# Mainboard.net
KiCad netlist of a schematic drawn in EAGLE
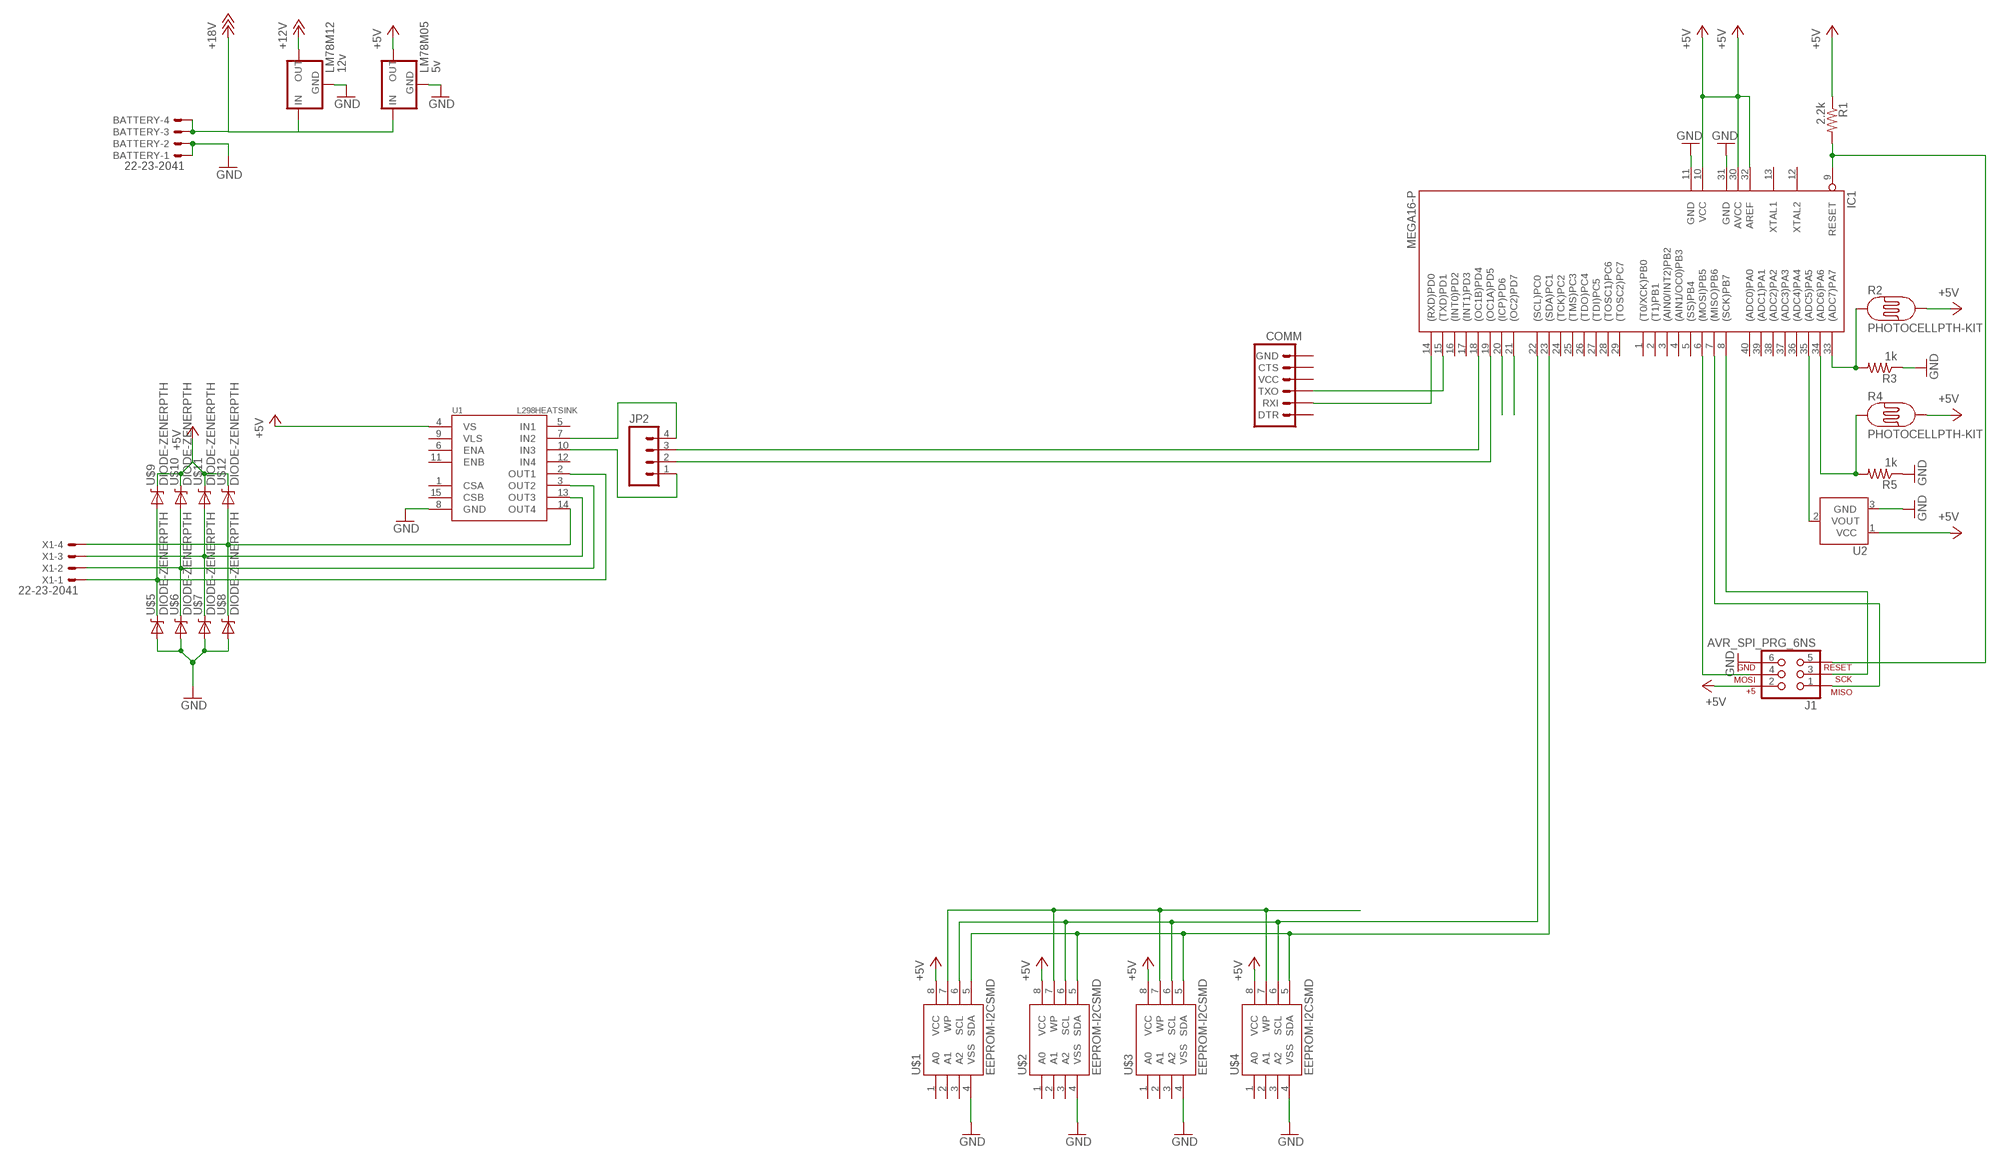
[diagram p0: schematic, sheet 1]

(export (version "E")
  (design (tool "Eeschema 10.0.6"))
  (components
    (comp (ref "BATTERY")
      (value "22-23-2041")
      (footprint "eagle-import:22-23-2041")
      (fields (field (name "MF") "MOLEX"))
      (libsource (lib "eagle-import") (part "22-23-2041"))
    )
    (comp (ref "COMM")
      (value "ARDUINO_SERIAL_PROGRAMPTH")
      (footprint "eagle-import:1X06")
      (libsource (lib "eagle-import") (part "ARDUINO_SERIAL_PROGRAMPTH"))
    )
    (comp (ref "IC1")
      (value "MEGA16-P")
      (footprint "eagle-import:DIL40")
      (fields (field (name "MPN") "ATMEGA16-16PU"))
      (libsource (lib "eagle-import") (part "MEGA16-P"))
    )
    (comp (ref "J1")
      (value "AVR_SPI_PRG_6NS")
      (footprint "eagle-import:2X3-NS")
      (libsource (lib "eagle-import") (part "AVR_SPI_PRG_6NS"))
    )
    (comp (ref "JP2")
      (value "M04PTH")
      (footprint "eagle-import:1X04")
      (libsource (lib "eagle-import") (part "M04PTH"))
    )
    (comp (ref "LM78M05")
      (value "5v")
      (footprint "eagle-import:78MXXL")
      (libsource (lib "eagle-import") (part "78MXXL"))
    )
    (comp (ref "LM78M12")
      (value "12v")
      (footprint "eagle-import:78MXXL")
      (libsource (lib "eagle-import") (part "78MXXL"))
    )
    (comp (ref "R1")
      (value "2.2k")
      (footprint "eagle-import:AXIAL-0.3")
      (libsource (lib "eagle-import") (part "RESISTORAXIAL-0.3"))
    )
    (comp (ref "R2")
      (value "PHOTOCELLPTH-KIT")
      (footprint "eagle-import:PHOTOCELL-KIT")
      (libsource (lib "eagle-import") (part "PHOTOCELLPTH-KIT"))
    )
    (comp (ref "R3")
      (value "1k")
      (footprint "eagle-import:AXIAL-0.3-KIT")
      (libsource (lib "eagle-import") (part "RESISTORKIT"))
    )
    (comp (ref "R4")
      (value "PHOTOCELLPTH-KIT")
      (footprint "eagle-import:PHOTOCELL-KIT")
      (libsource (lib "eagle-import") (part "PHOTOCELLPTH-KIT"))
    )
    (comp (ref "R5")
      (value "1k")
      (footprint "eagle-import:AXIAL-0.3-KIT")
      (libsource (lib "eagle-import") (part "RESISTORKIT"))
    )
    (comp (ref "U$1")
      (value "EEPROM-I2CSMD")
      (footprint "eagle-import:SO08")
      (libsource (lib "eagle-import") (part "EEPROM-I2CSMD"))
    )
    (comp (ref "U$2")
      (value "EEPROM-I2CSMD")
      (footprint "eagle-import:SO08")
      (libsource (lib "eagle-import") (part "EEPROM-I2CSMD"))
    )
    (comp (ref "U$3")
      (value "EEPROM-I2CSMD")
      (footprint "eagle-import:SO08")
      (libsource (lib "eagle-import") (part "EEPROM-I2CSMD"))
    )
    (comp (ref "U$4")
      (value "EEPROM-I2CSMD")
      (footprint "eagle-import:SO08")
      (libsource (lib "eagle-import") (part "EEPROM-I2CSMD"))
    )
    (comp (ref "U$5")
      (value "DIODE-ZENERPTH")
      (footprint "eagle-import:DIODE-ZENER")
      (libsource (lib "eagle-import") (part "DIODE-ZENERPTH"))
    )
    (comp (ref "U$6")
      (value "DIODE-ZENERPTH")
      (footprint "eagle-import:DIODE-ZENER")
      (libsource (lib "eagle-import") (part "DIODE-ZENERPTH"))
    )
    (comp (ref "U$7")
      (value "DIODE-ZENERPTH")
      (footprint "eagle-import:DIODE-ZENER")
      (libsource (lib "eagle-import") (part "DIODE-ZENERPTH"))
    )
    (comp (ref "U$8")
      (value "DIODE-ZENERPTH")
      (footprint "eagle-import:DIODE-ZENER")
      (libsource (lib "eagle-import") (part "DIODE-ZENERPTH"))
    )
    (comp (ref "U$9")
      (value "DIODE-ZENERPTH")
      (footprint "eagle-import:DIODE-ZENER")
      (libsource (lib "eagle-import") (part "DIODE-ZENERPTH"))
    )
    (comp (ref "U$10")
      (value "DIODE-ZENERPTH")
      (footprint "eagle-import:DIODE-ZENER")
      (libsource (lib "eagle-import") (part "DIODE-ZENERPTH"))
    )
    (comp (ref "U$11")
      (value "DIODE-ZENERPTH")
      (footprint "eagle-import:DIODE-ZENER")
      (libsource (lib "eagle-import") (part "DIODE-ZENERPTH"))
    )
    (comp (ref "U$12")
      (value "DIODE-ZENERPTH")
      (footprint "eagle-import:DIODE-ZENER")
      (libsource (lib "eagle-import") (part "DIODE-ZENERPTH"))
    )
    (comp (ref "U1")
      (value "L298HEATSINK")
      (footprint "eagle-import:MULTIWATT15_6400BGHEATSINK")
      (libsource (lib "eagle-import") (part "L298HEATSINK"))
    )
    (comp (ref "U2")
      (value "TMP36TO-92-KIT")
      (footprint "eagle-import:TO-92-KIT")
      (libsource (lib "eagle-import") (part "TMP36TO-92-KIT"))
    )
    (comp (ref "X1")
      (value "22-23-2041")
      (footprint "eagle-import:22-23-2041")
      (fields (field (name "MF") "MOLEX"))
      (libsource (lib "eagle-import") (part "22-23-2041"))
    )
  )
  (nets
    (net (code "1") (name "+5V") (class "Default")
      (node (ref "IC1") (pin "10") (pinfunction "VCC_10") (pintype "power_in"))
      (node (ref "IC1") (pin "30") (pinfunction "AVCC_30") (pintype "power_in"))
      (node (ref "IC1") (pin "32") (pinfunction "AREF_32") (pintype "passive"))
      (node (ref "J1") (pin "2") (pinfunction "2_2") (pintype "passive"))
      (node (ref "LM78M05") (pin "OUT") (pinfunction "OUT_OUT") (pintype "passive"))
      (node (ref "R1") (pin "P$1") (pinfunction "1_P$1") (pintype "passive"))
      (node (ref "R2") (pin "2") (pinfunction "P$2_2") (pintype "bidirectional"))
      (node (ref "R4") (pin "2") (pinfunction "P$2_2") (pintype "bidirectional"))
      (node (ref "U$1") (pin "8") (pinfunction "VCC_8") (pintype "power_in"))
      (node (ref "U$10") (pin "P$1") (pinfunction "C_P$1") (pintype "passive"))
      (node (ref "U$11") (pin "P$1") (pinfunction "C_P$1") (pintype "passive"))
      (node (ref "U$12") (pin "P$1") (pinfunction "C_P$1") (pintype "passive"))
      (node (ref "U$2") (pin "8") (pinfunction "VCC_8") (pintype "power_in"))
      (node (ref "U$3") (pin "8") (pinfunction "VCC_8") (pintype "power_in"))
      (node (ref "U$4") (pin "8") (pinfunction "VCC_8") (pintype "power_in"))
      (node (ref "U$9") (pin "P$1") (pinfunction "C_P$1") (pintype "passive"))
      (node (ref "U1") (pin "4") (pinfunction "VS_4") (pintype "bidirectional"))
      (node (ref "U2") (pin "1") (pinfunction "VCC_1") (pintype "bidirectional"))
    )
    (net (code "2") (name "+12V") (class "Default")
      (node (ref "LM78M12") (pin "OUT") (pinfunction "OUT_OUT") (pintype "passive"))
    )
    (net (code "3") (name "+18V") (class "Default")
      (node (ref "BATTERY") (pin "3") (pinfunction "S_3") (pintype "passive"))
      (node (ref "BATTERY") (pin "4") (pinfunction "S_4") (pintype "passive"))
      (node (ref "LM78M05") (pin "IN") (pinfunction "IN_IN") (pintype "input"))
      (node (ref "LM78M12") (pin "IN") (pinfunction "IN_IN") (pintype "input"))
    )
    (net (code "4") (name "GND") (class "Default")
      (node (ref "BATTERY") (pin "1") (pinfunction "S_1") (pintype "passive"))
      (node (ref "BATTERY") (pin "2") (pinfunction "S_2") (pintype "passive"))
      (node (ref "IC1") (pin "11") (pinfunction "GND_11") (pintype "power_in"))
      (node (ref "IC1") (pin "31") (pinfunction "GND_31") (pintype "power_in"))
      (node (ref "J1") (pin "6") (pinfunction "6_6") (pintype "passive"))
      (node (ref "LM78M05") (pin "GND") (pinfunction "GND_GND") (pintype "input"))
      (node (ref "LM78M12") (pin "GND") (pinfunction "GND_GND") (pintype "input"))
      (node (ref "R3") (pin "P$1") (pinfunction "1_P$1") (pintype "passive"))
      (node (ref "R5") (pin "P$1") (pinfunction "1_P$1") (pintype "passive"))
      (node (ref "U$1") (pin "4") (pinfunction "VSS_4") (pintype "power_in"))
      (node (ref "U$2") (pin "4") (pinfunction "VSS_4") (pintype "power_in"))
      (node (ref "U$3") (pin "4") (pinfunction "VSS_4") (pintype "power_in"))
      (node (ref "U$4") (pin "4") (pinfunction "VSS_4") (pintype "power_in"))
      (node (ref "U$5") (pin "P$2") (pinfunction "A_P$2") (pintype "passive"))
      (node (ref "U$6") (pin "P$2") (pinfunction "A_P$2") (pintype "passive"))
      (node (ref "U$7") (pin "P$2") (pinfunction "A_P$2") (pintype "passive"))
      (node (ref "U$8") (pin "P$2") (pinfunction "A_P$2") (pintype "passive"))
      (node (ref "U1") (pin "8") (pinfunction "GND_8") (pintype "bidirectional"))
      (node (ref "U2") (pin "3") (pinfunction "GND_3") (pintype "bidirectional"))
    )
    (net (code "5") (name "Net-(COMM-RXI)") (class "Default")
      (node (ref "COMM") (pin "2") (pinfunction "RXI_2") (pintype "passive"))
      (node (ref "IC1") (pin "14") (pinfunction "(RXD)PD0_14") (pintype "bidirectional"))
    )
    (net (code "6") (name "Net-(COMM-TXO)") (class "Default")
      (node (ref "COMM") (pin "3") (pinfunction "TXO_3") (pintype "passive"))
      (node (ref "IC1") (pin "15") (pinfunction "(TXD)PD1_15") (pintype "bidirectional"))
    )
    (net (code "7") (name "Net-(IC1-(ADC5)PA5)") (class "Default")
      (node (ref "IC1") (pin "35") (pinfunction "(ADC5)PA5_35") (pintype "bidirectional"))
      (node (ref "U2") (pin "2") (pinfunction "VOUT_2") (pintype "bidirectional"))
    )
    (net (code "8") (name "Net-(IC1-(ADC6)PA6)") (class "Default")
      (node (ref "IC1") (pin "34") (pinfunction "(ADC6)PA6_34") (pintype "bidirectional"))
      (node (ref "R4") (pin "1") (pinfunction "P$1_1") (pintype "bidirectional"))
      (node (ref "R5") (pin "P$2") (pinfunction "2_P$2") (pintype "passive"))
    )
    (net (code "9") (name "Net-(IC1-(ADC7)PA7)") (class "Default")
      (node (ref "IC1") (pin "33") (pinfunction "(ADC7)PA7_33") (pintype "bidirectional"))
      (node (ref "R2") (pin "1") (pinfunction "P$1_1") (pintype "bidirectional"))
      (node (ref "R3") (pin "P$2") (pinfunction "2_P$2") (pintype "passive"))
    )
    (net (code "10") (name "Net-(IC1-(MISO)PB6)") (class "Default")
      (node (ref "IC1") (pin "7") (pinfunction "(MISO)PB6_7") (pintype "bidirectional"))
      (node (ref "J1") (pin "1") (pinfunction "1_1") (pintype "passive"))
    )
    (net (code "11") (name "Net-(IC1-(MOSI)PB5)") (class "Default")
      (node (ref "IC1") (pin "6") (pinfunction "(MOSI)PB5_6") (pintype "bidirectional"))
      (node (ref "J1") (pin "4") (pinfunction "4_4") (pintype "passive"))
    )
    (net (code "12") (name "Net-(IC1-(OC1A)PD5)") (class "Default")
      (node (ref "IC1") (pin "19") (pinfunction "(OC1A)PD5_19") (pintype "bidirectional"))
      (node (ref "JP2") (pin "2") (pinfunction "2_2") (pintype "passive"))
    )
    (net (code "13") (name "Net-(IC1-(OC1B)PD4)") (class "Default")
      (node (ref "IC1") (pin "18") (pinfunction "(OC1B)PD4_18") (pintype "bidirectional"))
      (node (ref "JP2") (pin "3") (pinfunction "3_3") (pintype "passive"))
    )
    (net (code "14") (name "Net-(IC1-(SCK)PB7)") (class "Default")
      (node (ref "IC1") (pin "8") (pinfunction "(SCK)PB7_8") (pintype "bidirectional"))
      (node (ref "J1") (pin "3") (pinfunction "3_3") (pintype "passive"))
    )
    (net (code "15") (name "Net-(IC1-(SCL)PC0)") (class "Default")
      (node (ref "IC1") (pin "22") (pinfunction "(SCL)PC0_22") (pintype "bidirectional"))
      (node (ref "U$1") (pin "6") (pinfunction "SCL_6") (pintype "bidirectional"))
      (node (ref "U$2") (pin "6") (pinfunction "SCL_6") (pintype "bidirectional"))
      (node (ref "U$3") (pin "6") (pinfunction "SCL_6") (pintype "bidirectional"))
      (node (ref "U$4") (pin "6") (pinfunction "SCL_6") (pintype "bidirectional"))
    )
    (net (code "16") (name "Net-(IC1-(SDA)PC1)") (class "Default")
      (node (ref "IC1") (pin "23") (pinfunction "(SDA)PC1_23") (pintype "bidirectional"))
      (node (ref "U$1") (pin "5") (pinfunction "SDA_5") (pintype "bidirectional"))
      (node (ref "U$2") (pin "5") (pinfunction "SDA_5") (pintype "bidirectional"))
      (node (ref "U$3") (pin "5") (pinfunction "SDA_5") (pintype "bidirectional"))
      (node (ref "U$4") (pin "5") (pinfunction "SDA_5") (pintype "bidirectional"))
    )
    (net (code "17") (name "Net-(IC1-RESET)") (class "Default")
      (node (ref "IC1") (pin "9") (pinfunction "RESET_9") (pintype "input"))
      (node (ref "J1") (pin "5") (pinfunction "5_5") (pintype "passive"))
      (node (ref "R1") (pin "P$2") (pinfunction "2_P$2") (pintype "passive"))
    )
    (net (code "18") (name "Net-(U$1-WP)") (class "Default")
      (node (ref "U$1") (pin "7") (pinfunction "WP_7") (pintype "bidirectional"))
      (node (ref "U$2") (pin "7") (pinfunction "WP_7") (pintype "bidirectional"))
      (node (ref "U$3") (pin "7") (pinfunction "WP_7") (pintype "bidirectional"))
      (node (ref "U$4") (pin "7") (pinfunction "WP_7") (pintype "bidirectional"))
    )
    (net (code "19") (name "Net-(U$5-C)") (class "Default")
      (node (ref "U$5") (pin "P$1") (pinfunction "C_P$1") (pintype "passive"))
      (node (ref "U$9") (pin "P$2") (pinfunction "A_P$2") (pintype "passive"))
      (node (ref "U1") (pin "2") (pinfunction "OUT1_2") (pintype "bidirectional"))
      (node (ref "X1") (pin "1") (pinfunction "S_1") (pintype "passive"))
    )
    (net (code "20") (name "Net-(U$10-A)") (class "Default")
      (node (ref "U$10") (pin "P$2") (pinfunction "A_P$2") (pintype "passive"))
      (node (ref "U$6") (pin "P$1") (pinfunction "C_P$1") (pintype "passive"))
      (node (ref "U1") (pin "3") (pinfunction "OUT2_3") (pintype "bidirectional"))
      (node (ref "X1") (pin "2") (pinfunction "S_2") (pintype "passive"))
    )
    (net (code "21") (name "Net-(U$11-A)") (class "Default")
      (node (ref "U$11") (pin "P$2") (pinfunction "A_P$2") (pintype "passive"))
      (node (ref "U$7") (pin "P$1") (pinfunction "C_P$1") (pintype "passive"))
      (node (ref "U1") (pin "13") (pinfunction "OUT3_13") (pintype "bidirectional"))
      (node (ref "X1") (pin "3") (pinfunction "S_3") (pintype "passive"))
    )
    (net (code "22") (name "Net-(U$12-A)") (class "Default")
      (node (ref "U$12") (pin "P$2") (pinfunction "A_P$2") (pintype "passive"))
      (node (ref "U$8") (pin "P$1") (pinfunction "C_P$1") (pintype "passive"))
      (node (ref "U1") (pin "14") (pinfunction "OUT4_14") (pintype "bidirectional"))
      (node (ref "X1") (pin "4") (pinfunction "S_4") (pintype "passive"))
    )
    (net (code "23") (name "Net-(U1-IN2)") (class "Default")
      (node (ref "JP2") (pin "4") (pinfunction "4_4") (pintype "passive"))
      (node (ref "U1") (pin "7") (pinfunction "IN2_7") (pintype "bidirectional"))
    )
    (net (code "24") (name "Net-(U1-IN3)") (class "Default")
      (node (ref "JP2") (pin "1") (pinfunction "1_1") (pintype "passive"))
      (node (ref "U1") (pin "10") (pinfunction "IN3_10") (pintype "bidirectional"))
    )
    (net (code "25") (name "unconnected-(COMM-CTS-Pad5)") (class "Default")
      (node (ref "COMM") (pin "5") (pinfunction "CTS_5") (pintype "passive"))
    )
    (net (code "26") (name "unconnected-(COMM-DTR-Pad1)") (class "Default")
      (node (ref "COMM") (pin "1") (pinfunction "DTR_1") (pintype "passive"))
    )
    (net (code "27") (name "unconnected-(COMM-GND-Pad6)") (class "Default")
      (node (ref "COMM") (pin "6") (pinfunction "GND_6") (pintype "passive"))
    )
    (net (code "28") (name "unconnected-(COMM-VCC-Pad4)") (class "Default")
      (node (ref "COMM") (pin "4") (pinfunction "VCC_4") (pintype "passive"))
    )
    (net (code "29") (name "unconnected-(IC1-(ADC0)PA0-Pad40)") (class "Default")
      (node (ref "IC1") (pin "40") (pinfunction "(ADC0)PA0_40") (pintype "bidirectional"))
    )
    (net (code "30") (name "unconnected-(IC1-(ADC1)PA1-Pad39)") (class "Default")
      (node (ref "IC1") (pin "39") (pinfunction "(ADC1)PA1_39") (pintype "bidirectional"))
    )
    (net (code "31") (name "unconnected-(IC1-(ADC2)PA2-Pad38)") (class "Default")
      (node (ref "IC1") (pin "38") (pinfunction "(ADC2)PA2_38") (pintype "bidirectional"))
    )
    (net (code "32") (name "unconnected-(IC1-(ADC3)PA3-Pad37)") (class "Default")
      (node (ref "IC1") (pin "37") (pinfunction "(ADC3)PA3_37") (pintype "bidirectional"))
    )
    (net (code "33") (name "unconnected-(IC1-(ADC4)PA4-Pad36)") (class "Default")
      (node (ref "IC1") (pin "36") (pinfunction "(ADC4)PA4_36") (pintype "bidirectional"))
    )
    (net (code "34") (name "unconnected-(IC1-(AIN0{slash}INT2)PB2-Pad3)") (class "Default")
      (node (ref "IC1") (pin "3") (pinfunction "(AIN0/INT2)PB2_3") (pintype "bidirectional"))
    )
    (net (code "35") (name "unconnected-(IC1-(AIN1{slash}OC0)PB3-Pad4)") (class "Default")
      (node (ref "IC1") (pin "4") (pinfunction "(AIN1/OC0)PB3_4") (pintype "bidirectional"))
    )
    (net (code "36") (name "unconnected-(IC1-(ICP)PD6-Pad20)") (class "Default")
      (node (ref "IC1") (pin "20") (pinfunction "(ICP)PD6_20") (pintype "bidirectional"))
    )
    (net (code "37") (name "unconnected-(IC1-(INT0)PD2-Pad16)") (class "Default")
      (node (ref "IC1") (pin "16") (pinfunction "(INT0)PD2_16") (pintype "bidirectional"))
    )
    (net (code "38") (name "unconnected-(IC1-(INT1)PD3-Pad17)") (class "Default")
      (node (ref "IC1") (pin "17") (pinfunction "(INT1)PD3_17") (pintype "bidirectional"))
    )
    (net (code "39") (name "unconnected-(IC1-(OC2)PD7-Pad21)") (class "Default")
      (node (ref "IC1") (pin "21") (pinfunction "(OC2)PD7_21") (pintype "bidirectional"))
    )
    (net (code "40") (name "unconnected-(IC1-(SS)PB4-Pad5)") (class "Default")
      (node (ref "IC1") (pin "5") (pinfunction "(SS)PB4_5") (pintype "bidirectional"))
    )
    (net (code "41") (name "unconnected-(IC1-(T0{slash}XCK)PB0-Pad1)") (class "Default")
      (node (ref "IC1") (pin "1") (pinfunction "(T0/XCK)PB0_1") (pintype "bidirectional"))
    )
    (net (code "42") (name "unconnected-(IC1-(T1)PB1-Pad2)") (class "Default")
      (node (ref "IC1") (pin "2") (pinfunction "(T1)PB1_2") (pintype "bidirectional"))
    )
    (net (code "43") (name "unconnected-(IC1-(TCK)PC2-Pad24)") (class "Default")
      (node (ref "IC1") (pin "24") (pinfunction "(TCK)PC2_24") (pintype "bidirectional"))
    )
    (net (code "44") (name "unconnected-(IC1-(TDI)PC5-Pad27)") (class "Default")
      (node (ref "IC1") (pin "27") (pinfunction "(TDI)PC5_27") (pintype "bidirectional"))
    )
    (net (code "45") (name "unconnected-(IC1-(TDO)PC4-Pad26)") (class "Default")
      (node (ref "IC1") (pin "26") (pinfunction "(TDO)PC4_26") (pintype "bidirectional"))
    )
    (net (code "46") (name "unconnected-(IC1-(TMS)PC3-Pad25)") (class "Default")
      (node (ref "IC1") (pin "25") (pinfunction "(TMS)PC3_25") (pintype "bidirectional"))
    )
    (net (code "47") (name "unconnected-(IC1-(TOSC1)PC6-Pad28)") (class "Default")
      (node (ref "IC1") (pin "28") (pinfunction "(TOSC1)PC6_28") (pintype "bidirectional"))
    )
    (net (code "48") (name "unconnected-(IC1-(TOSC2)PC7-Pad29)") (class "Default")
      (node (ref "IC1") (pin "29") (pinfunction "(TOSC2)PC7_29") (pintype "bidirectional"))
    )
    (net (code "49") (name "unconnected-(IC1-XTAL1-Pad13)") (class "Default")
      (node (ref "IC1") (pin "13") (pinfunction "XTAL1_13") (pintype "bidirectional"))
    )
    (net (code "50") (name "unconnected-(IC1-XTAL2-Pad12)") (class "Default")
      (node (ref "IC1") (pin "12") (pinfunction "XTAL2_12") (pintype "bidirectional"))
    )
    (net (code "51") (name "unconnected-(U$1-A0-Pad1)") (class "Default")
      (node (ref "U$1") (pin "1") (pinfunction "A0_1") (pintype "bidirectional"))
    )
    (net (code "52") (name "unconnected-(U$1-A1-Pad2)") (class "Default")
      (node (ref "U$1") (pin "2") (pinfunction "A1_2") (pintype "bidirectional"))
    )
    (net (code "53") (name "unconnected-(U$1-A2-Pad3)") (class "Default")
      (node (ref "U$1") (pin "3") (pinfunction "A2_3") (pintype "bidirectional"))
    )
    (net (code "54") (name "unconnected-(U$2-A0-Pad1)") (class "Default")
      (node (ref "U$2") (pin "1") (pinfunction "A0_1") (pintype "bidirectional"))
    )
    (net (code "55") (name "unconnected-(U$2-A1-Pad2)") (class "Default")
      (node (ref "U$2") (pin "2") (pinfunction "A1_2") (pintype "bidirectional"))
    )
    (net (code "56") (name "unconnected-(U$2-A2-Pad3)") (class "Default")
      (node (ref "U$2") (pin "3") (pinfunction "A2_3") (pintype "bidirectional"))
    )
    (net (code "57") (name "unconnected-(U$3-A0-Pad1)") (class "Default")
      (node (ref "U$3") (pin "1") (pinfunction "A0_1") (pintype "bidirectional"))
    )
    (net (code "58") (name "unconnected-(U$3-A1-Pad2)") (class "Default")
      (node (ref "U$3") (pin "2") (pinfunction "A1_2") (pintype "bidirectional"))
    )
    (net (code "59") (name "unconnected-(U$3-A2-Pad3)") (class "Default")
      (node (ref "U$3") (pin "3") (pinfunction "A2_3") (pintype "bidirectional"))
    )
    (net (code "60") (name "unconnected-(U$4-A0-Pad1)") (class "Default")
      (node (ref "U$4") (pin "1") (pinfunction "A0_1") (pintype "bidirectional"))
    )
    (net (code "61") (name "unconnected-(U$4-A1-Pad2)") (class "Default")
      (node (ref "U$4") (pin "2") (pinfunction "A1_2") (pintype "bidirectional"))
    )
    (net (code "62") (name "unconnected-(U$4-A2-Pad3)") (class "Default")
      (node (ref "U$4") (pin "3") (pinfunction "A2_3") (pintype "bidirectional"))
    )
    (net (code "63") (name "unconnected-(U1-CSA-Pad1)") (class "Default")
      (node (ref "U1") (pin "1") (pinfunction "CSA_1") (pintype "bidirectional"))
    )
    (net (code "64") (name "unconnected-(U1-CSB-Pad15)") (class "Default")
      (node (ref "U1") (pin "15") (pinfunction "CSB_15") (pintype "bidirectional"))
    )
    (net (code "65") (name "unconnected-(U1-ENA-Pad6)") (class "Default")
      (node (ref "U1") (pin "6") (pinfunction "ENA_6") (pintype "bidirectional"))
    )
    (net (code "66") (name "unconnected-(U1-ENB-Pad11)") (class "Default")
      (node (ref "U1") (pin "11") (pinfunction "ENB_11") (pintype "bidirectional"))
    )
    (net (code "67") (name "unconnected-(U1-IN1-Pad5)") (class "Default")
      (node (ref "U1") (pin "5") (pinfunction "IN1_5") (pintype "bidirectional"))
    )
    (net (code "68") (name "unconnected-(U1-IN4-Pad12)") (class "Default")
      (node (ref "U1") (pin "12") (pinfunction "IN4_12") (pintype "bidirectional"))
    )
    (net (code "69") (name "unconnected-(U1-VLS-Pad9)") (class "Default")
      (node (ref "U1") (pin "9") (pinfunction "VLS_9") (pintype "bidirectional"))
    )
  )
)
